# Relay.net
KiCad netlist of a schematic drawn in Altium Designer
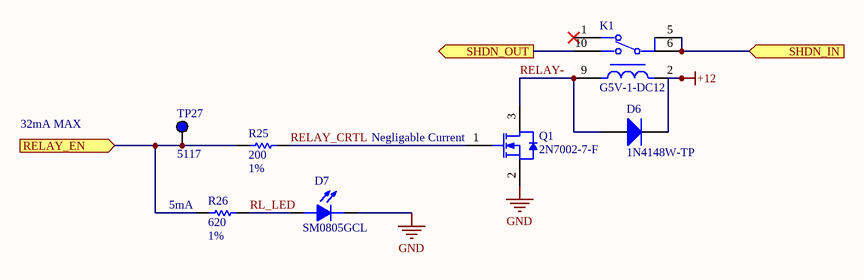
[diagram p0: Relay.SchDoc]

(export (version "E")
  (design (tool "Eeschema 10.0.6"))
  (components
    (comp (ref "D6")
      (value "1N4148W-TP")
      (footprint "MCC-SOD123_V")
      (description "High Speed Switching Diode, 400 mW, 150 mA, -65 to 150 degC, 2-Pin SOD123, RoHS, Tape and Reel")
      (fields (field (name "MANUFACTURER") "Micro Commercial Components"))
      (libsource (lib "Altium Content Vault") (part "D-AK-2"))
    )
    (comp (ref "D7")
      (value "SM0805GCL")
      (footprint "LEDC2012X135N_SM0805GCL(Primary)")
      (description "Green 574nm LED Indication - Discrete 1.9V 0805 (2012 Metric)")
      (libsource (lib "bspd parts") (part "SM0805GCL"))
    )
    (comp (ref "K1")
      (value "G5V-1-DC12")
      (footprint "Omron_G5V-1-DC12_MFG")
      (description "General Purpose Relay SPDT (1 Form C) Through Hole")
      (fields (field (name "DIGIKEY PART NUMBER") "Z774-ND") (field (name "MANUFACTURER") "Omron"))
      (libsource (lib "bspd parts") (part "G5V-1-DC12"))
    )
    (comp (ref "Q1")
      (value "2N7002-7-F")
      (footprint "DIOD-SOT23-3_V")
      (fields (field (name "MANUFACTURER") "DiodesIncorporated"))
      (libsource (lib "Altium Content Vault") (part "NEMOS-GSD-3"))
    )
    (comp (ref "R25")
      (value "RES 0603 200 1%")
      (footprint "0603_RES")
      (description "Resistor Surface Mount, 200 Ohms, 0603 Footprint, 1% Tolerance 0.1W")
      (fields
        (field (name "VAL") "200")
        (field (name "TOL") "1%")
        (field (name "MANUFACTURER") "Various")
        (field (name "TOLERANCE") "1%")
      )
      (libsource (lib "Passive Components") (part "res"))
    )
    (comp (ref "R26")
      (value "RES 0603 620 1%")
      (footprint "0603_RES")
      (description "Resistor Surface Mount, 620 Ohms, 0603 Footprint, 1% Tolerance 0.1W")
      (fields
        (field (name "VAL") "620")
        (field (name "TOL") "1%")
        (field (name "MANUFACTURER") "Various")
        (field (name "TOLERANCE") "1%")
      )
      (libsource (lib "Passive Components") (part "res"))
    )
    (comp (ref "TP27")
      (value "5117")
      (footprint "KSTN-5117")
      (description "Test Point, Blue, 1-Pin THD, RoHS, Bulk")
      (fields (field (name "MANUFACTURER") "KeystoneElectronics"))
      (libsource (lib "bspd parts") (part "5117"))
    )
  )
  (nets
    (net (code "1") (name "+12") (class "Default")
      (node (ref "D6") (pin "2") (pinfunction "K_2") (pintype "passive"))
      (node (ref "K1") (pin "2") (pinfunction "2_2") (pintype "passive"))
    )
    (net (code "2") (name "/RELAY-") (class "Default")
      (node (ref "D6") (pin "1") (pinfunction "A_1") (pintype "passive"))
      (node (ref "K1") (pin "9") (pinfunction "9_9") (pintype "passive"))
      (node (ref "Q1") (pin "3") (pinfunction "D_3") (pintype "passive"))
    )
    (net (code "3") (name "/RELAY_CRTL") (class "Default")
      (node (ref "Q1") (pin "1") (pinfunction "G_1") (pintype "passive"))
      (node (ref "R25") (pin "2") (pinfunction "2_2") (pintype "passive"))
    )
    (net (code "4") (name "/RELAY_EN") (class "Default")
      (node (ref "R25") (pin "1") (pinfunction "1_1") (pintype "passive"))
      (node (ref "R26") (pin "1") (pinfunction "1_1") (pintype "passive"))
      (node (ref "TP27") (pin "1") (pintype "passive"))
    )
    (net (code "5") (name "/RL_LED") (class "Default")
      (node (ref "D7") (pin "A") (pinfunction "A_A") (pintype "passive"))
      (node (ref "R26") (pin "2") (pinfunction "2_2") (pintype "passive"))
    )
    (net (code "6") (name "/SHDN_IN") (class "Default")
      (node (ref "K1") (pin "5") (pinfunction "5_5") (pintype "passive"))
      (node (ref "K1") (pin "6") (pinfunction "6_6") (pintype "passive"))
    )
    (net (code "7") (name "/SHDN_OUT") (class "Default")
      (node (ref "K1") (pin "10") (pinfunction "10_10") (pintype "passive"))
    )
    (net (code "8") (name "GND") (class "Default")
      (node (ref "D7") (pin "C") (pinfunction "C_C") (pintype "passive"))
      (node (ref "Q1") (pin "2") (pinfunction "S_2") (pintype "passive"))
    )
    (net (code "9") (name "unconnected-(K1-Pad1)") (class "Default")
      (node (ref "K1") (pin "1") (pinfunction "1_1") (pintype "passive+no_connect"))
    )
  )
)
